# HM-13.net
KiCad netlist of a schematic drawn in Altium Designer
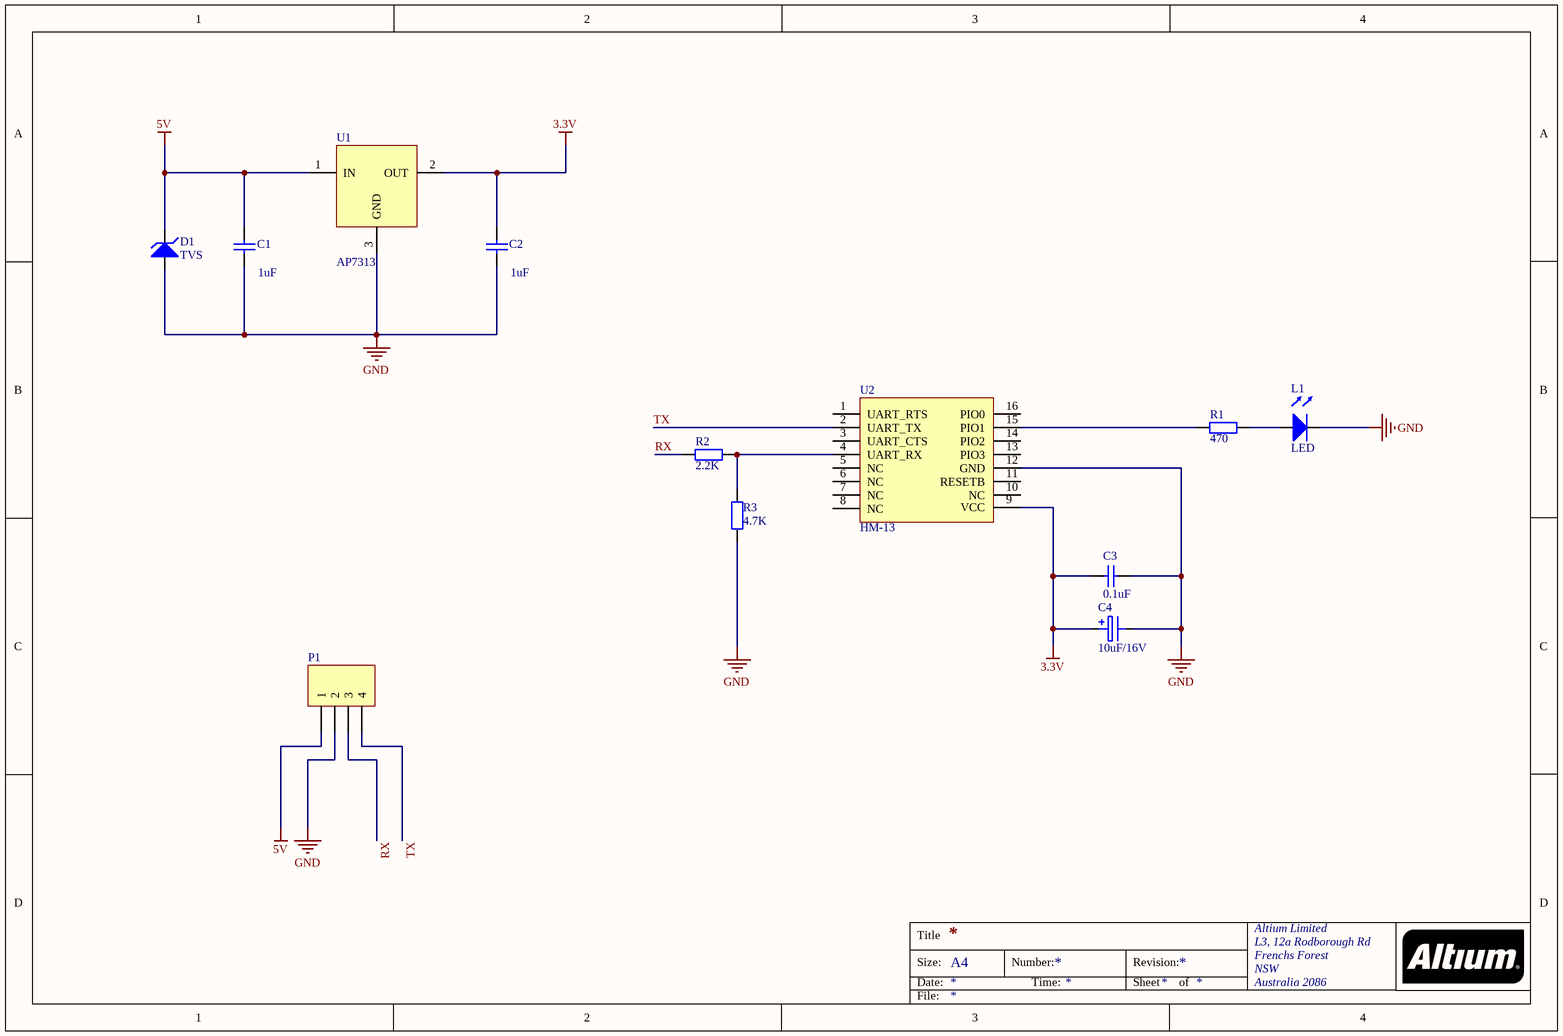
[diagram p0: HM-13.SchDoc]

(export (version "E")
  (design (tool "Eeschema 10.0.6"))
  (components
    (comp (ref "C1")
      (value "1uF")
      (footprint "0603")
      (description "ceramic")
      (libsource (lib "ToponLib") (part "Cap1"))
    )
    (comp (ref "C2")
      (value "1uF")
      (footprint "0603")
      (description "ceramic")
      (libsource (lib "ToponLib") (part "Cap1"))
    )
    (comp (ref "C3")
      (value "0.1uF")
      (footprint "0603")
      (description "ceramic")
      (libsource (lib "ToponLib") (part "Cap1"))
    )
    (comp (ref "C4")
      (value "10uF/16V")
      (footprint "1206")
      (description "aluminum")
      (libsource (lib "ToponLib") (part "Cap3"))
    )
    (comp (ref "D1") (value "TVS") (footprint "DO214-AC") (libsource (lib "ToponLib") (part "6V8A-TVS")))
    (comp (ref "L1") (value "LED") (footprint "0805") (libsource (lib "ToponLib") (part "LED")))
    (comp (ref "P1")
      (value "Header 4")
      (footprint "HDR1X4")
      (description "Header, 4-Pin")
      (fields (field (name "PUBLISHER") "Altium Limited"))
      (libsource (lib "Miscellaneous Connectors") (part "Header 4"))
    )
    (comp (ref "R1") (value "470") (footprint "0603") (libsource (lib "") (part "Res_2")))
    (comp (ref "R2") (value "2.2K") (footprint "0603") (libsource (lib "") (part "Res_1")))
    (comp (ref "R3") (value "4.7K") (footprint "0603") (libsource (lib "ToponLib") (part "Res")))
    (comp (ref "U1")
      (value "AP7313")
      (footprint "AP7313-33SAG-7")
      (libsource (lib "ToponLib") (part "AP7313-33SAG-7"))
    )
    (comp (ref "U2") (value "HM-13") (footprint "HM-13") (libsource (lib "ToponLib") (part "HM-13")))
  )
  (nets
    (net (code "1") (name "/RX") (class "Default")
      (node (ref "P1") (pin "3") (pinfunction "3_3") (pintype "passive"))
      (node (ref "R2") (pin "2") (pinfunction "2_2") (pintype "passive"))
    )
    (net (code "2") (name "/TX") (class "Default")
      (node (ref "P1") (pin "4") (pinfunction "4_4") (pintype "passive"))
      (node (ref "U2") (pin "2") (pinfunction "UART_TX_2") (pintype "passive"))
    )
    (net (code "3") (name "3.3V") (class "Default")
      (node (ref "C2") (pin "2") (pinfunction "2_2") (pintype "passive"))
      (node (ref "C3") (pin "2") (pinfunction "2_2") (pintype "passive"))
      (node (ref "C4") (pin "1") (pinfunction "1_1") (pintype "passive"))
      (node (ref "U1") (pin "2") (pinfunction "OUT_2") (pintype "passive"))
      (node (ref "U2") (pin "9") (pinfunction "VCC_9") (pintype "passive"))
    )
    (net (code "4") (name "5V") (class "Default")
      (node (ref "C1") (pin "2") (pinfunction "2_2") (pintype "passive"))
      (node (ref "D1") (pin "2") (pinfunction "K_2") (pintype "passive"))
      (node (ref "P1") (pin "1") (pinfunction "1_1") (pintype "passive"))
      (node (ref "U1") (pin "1") (pinfunction "IN_1") (pintype "passive"))
    )
    (net (code "5") (name "GND") (class "Default")
      (node (ref "C1") (pin "1") (pinfunction "1_1") (pintype "passive"))
      (node (ref "C2") (pin "1") (pinfunction "1_1") (pintype "passive"))
      (node (ref "C3") (pin "1") (pinfunction "1_1") (pintype "passive"))
      (node (ref "C4") (pin "2") (pinfunction "2_2") (pintype "passive"))
      (node (ref "D1") (pin "1") (pinfunction "A_1") (pintype "passive"))
      (node (ref "L1") (pin "2") (pinfunction "K_2") (pintype "passive"))
      (node (ref "P1") (pin "2") (pinfunction "2_2") (pintype "passive"))
      (node (ref "R3") (pin "1") (pinfunction "1_1") (pintype "passive"))
      (node (ref "U1") (pin "3") (pinfunction "GND_3") (pintype "passive"))
      (node (ref "U2") (pin "12") (pinfunction "GND_12") (pintype "passive"))
    )
    (net (code "6") (name "Net-(L1-A)") (class "Default")
      (node (ref "L1") (pin "1") (pinfunction "A_1") (pintype "passive"))
      (node (ref "R1") (pin "2") (pinfunction "2_2") (pintype "passive"))
    )
    (net (code "7") (name "Net-(U2-PIO1)") (class "Default")
      (node (ref "R1") (pin "1") (pinfunction "1_1") (pintype "passive"))
      (node (ref "U2") (pin "15") (pinfunction "PIO1_15") (pintype "passive"))
    )
    (net (code "8") (name "Net-(U2-UART_RX)") (class "Default")
      (node (ref "R2") (pin "1") (pinfunction "1_1") (pintype "passive"))
      (node (ref "R3") (pin "2") (pinfunction "2_2") (pintype "passive"))
      (node (ref "U2") (pin "4") (pinfunction "UART_RX_4") (pintype "passive"))
    )
    (net (code "9") (name "unconnected-(U2-NC-Pad5)") (class "Default")
      (node (ref "U2") (pin "5") (pinfunction "NC_5") (pintype "passive"))
    )
    (net (code "10") (name "unconnected-(U2-NC-Pad6)") (class "Default")
      (node (ref "U2") (pin "6") (pinfunction "NC_6") (pintype "passive"))
    )
    (net (code "11") (name "unconnected-(U2-NC-Pad7)") (class "Default")
      (node (ref "U2") (pin "7") (pinfunction "NC_7") (pintype "passive"))
    )
    (net (code "12") (name "unconnected-(U2-NC-Pad8)") (class "Default")
      (node (ref "U2") (pin "8") (pinfunction "NC_8") (pintype "passive"))
    )
    (net (code "13") (name "unconnected-(U2-NC-Pad10)") (class "Default")
      (node (ref "U2") (pin "10") (pinfunction "NC_10") (pintype "passive"))
    )
    (net (code "14") (name "unconnected-(U2-PIO0-Pad16)") (class "Default")
      (node (ref "U2") (pin "16") (pinfunction "PIO0_16") (pintype "passive"))
    )
    (net (code "15") (name "unconnected-(U2-PIO2-Pad14)") (class "Default")
      (node (ref "U2") (pin "14") (pinfunction "PIO2_14") (pintype "passive"))
    )
    (net (code "16") (name "unconnected-(U2-PIO3-Pad13)") (class "Default")
      (node (ref "U2") (pin "13") (pinfunction "PIO3_13") (pintype "passive"))
    )
    (net (code "17") (name "unconnected-(U2-RESETB-Pad11)") (class "Default")
      (node (ref "U2") (pin "11") (pinfunction "RESETB_11") (pintype "passive"))
    )
    (net (code "18") (name "unconnected-(U2-UART_CTS-Pad3)") (class "Default")
      (node (ref "U2") (pin "3") (pinfunction "UART_CTS_3") (pintype "passive"))
    )
    (net (code "19") (name "unconnected-(U2-UART_RTS-Pad1)") (class "Default")
      (node (ref "U2") (pin "1") (pinfunction "UART_RTS_1") (pintype "passive"))
    )
  )
)
